# Base_station_Unit_board.net
KiCad netlist of a schematic drawn in Altium Designer
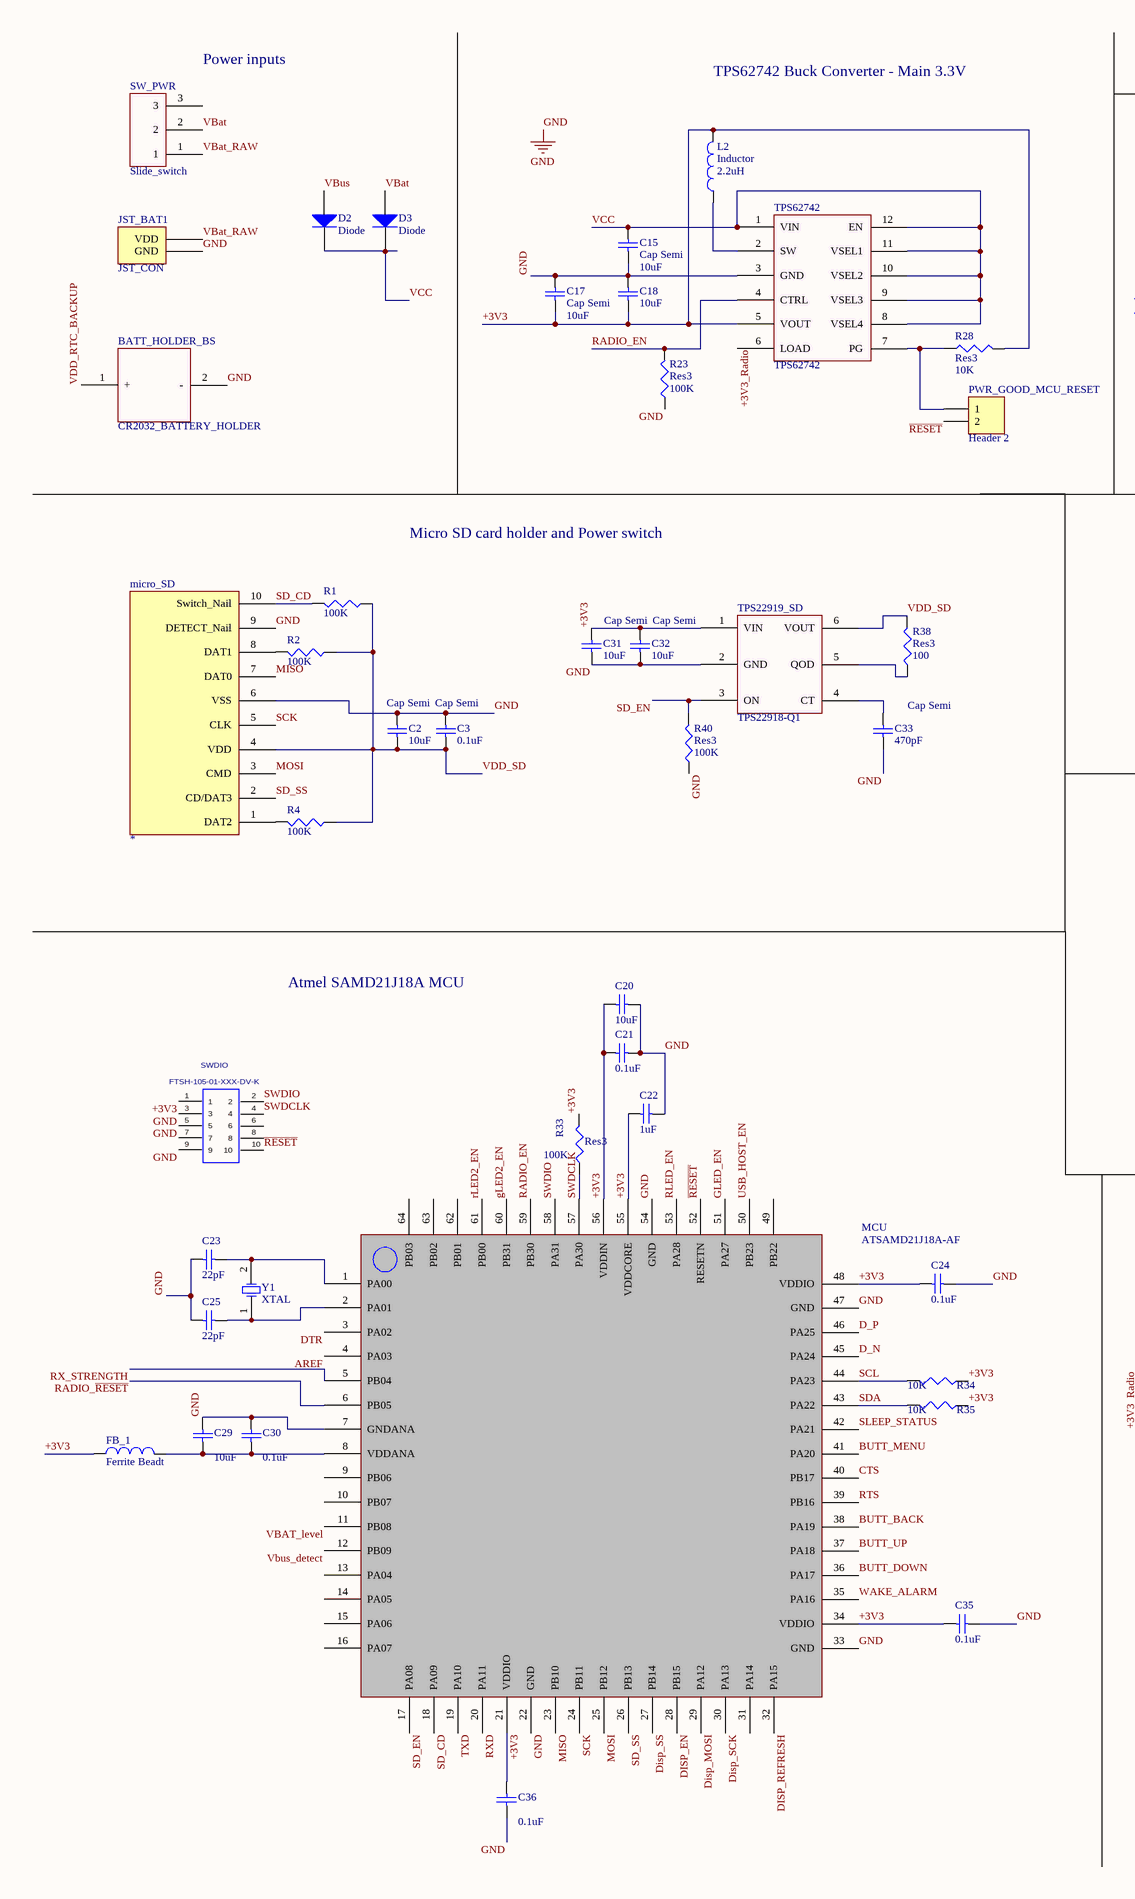
[diagram p0: Base_station_Unit_board.SchDoc, left]
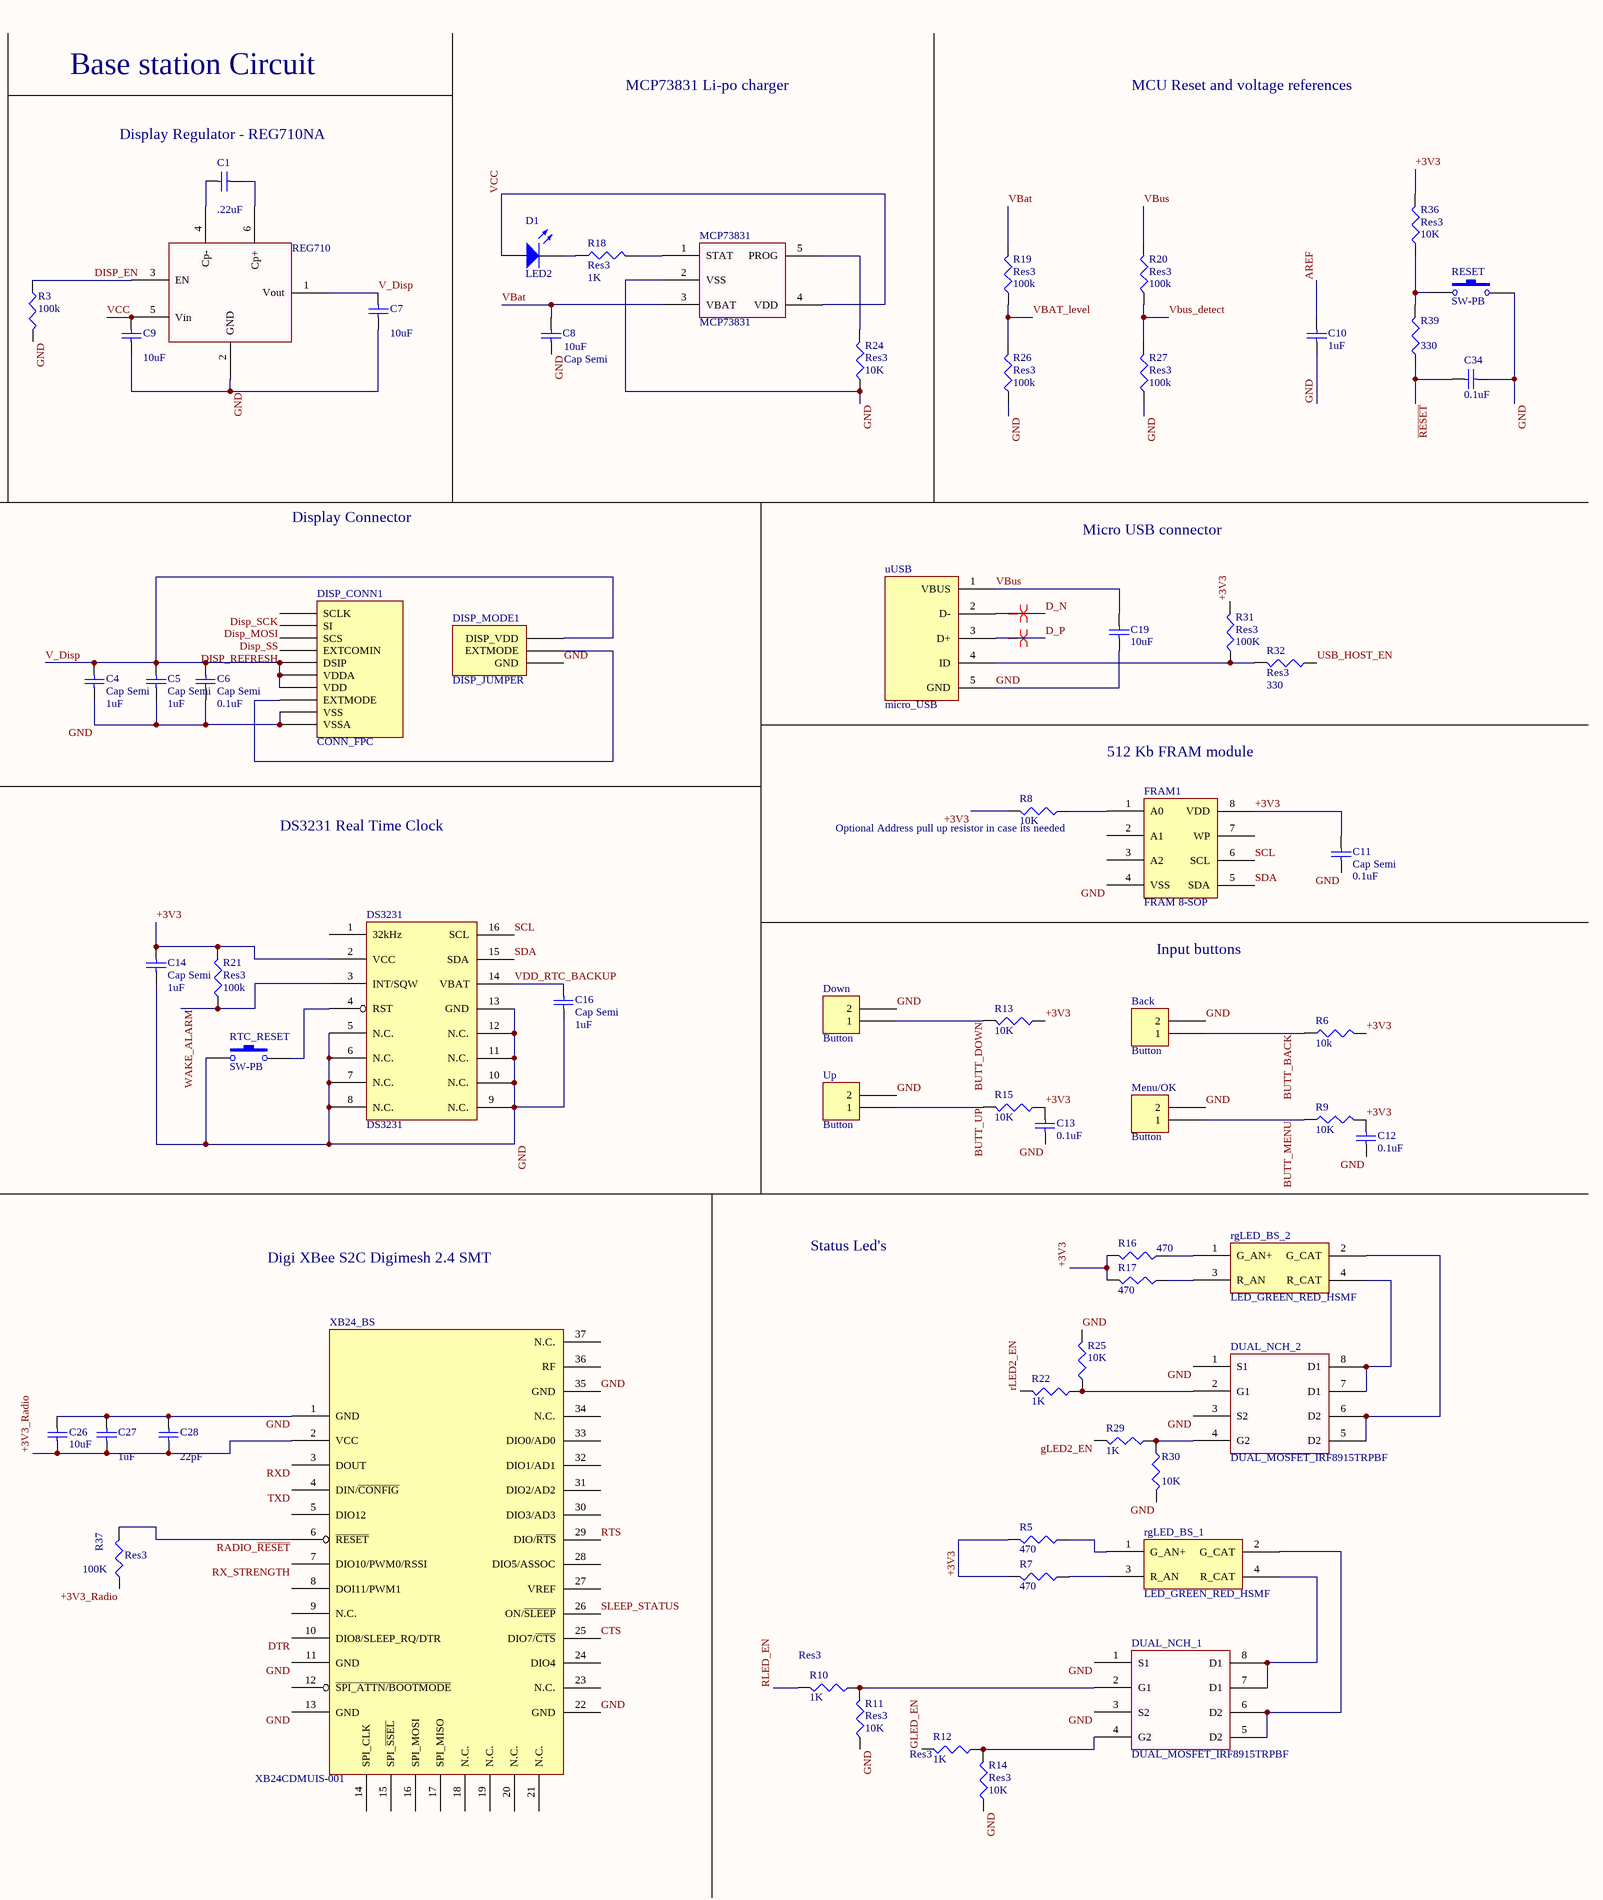
[diagram p1: Base_station_Unit_board.SchDoc, right]

(export (version "E")
  (design (tool "Eeschema 10.0.6"))
  (components
    (comp (ref "Back")
      (value "Button")
      (footprint "EVPASCB1A - Tactile Switch")
      (libsource (lib "Parts_Schematic") (part "Button"))
    )
    (comp (ref "BATT_HOLDER_BS")
      (value "CR2032_BATTERY_HOLDER")
      (footprint "CR1220_clip")
      (libsource (lib "SMD_components") (part "CR2032_BATTERY_HOLDER"))
    )
    (comp (ref "C1")
      (value ".22uF")
      (footprint "C0805")
      (description "Capacitor (Semiconductor SIM Model)")
      (fields (field (name "Comment") "Cap Semi") (field (name "PUBLISHER") "Altium Limited"))
      (libsource (lib "Miscellaneous Devices") (part "Cap Semi"))
    )
    (comp (ref "C2")
      (value "Cap Semi")
      (footprint "1608[0603]")
      (description "Capacitor (Semiconductor SIM Model)")
      (fields (field (name "ALTIUM_VALUE") "10uF") (field (name "PUBLISHER") "Altium Limited"))
      (libsource (lib "Miscellaneous Devices") (part "Cap Semi"))
    )
    (comp (ref "C3")
      (value "Cap Semi")
      (footprint "C0805")
      (description "Capacitor (Semiconductor SIM Model)")
      (fields (field (name "ALTIUM_VALUE") "0.1uF") (field (name "PUBLISHER") "Altium Limited"))
      (libsource (lib "Miscellaneous Devices") (part "Cap Semi"))
    )
    (comp (ref "C4")
      (value "Cap Semi")
      (footprint "C0805")
      (description "Capacitor (Semiconductor SIM Model)")
      (fields (field (name "ALTIUM_VALUE") "1uF") (field (name "PUBLISHER") "Altium Limited"))
      (libsource (lib "Miscellaneous Devices") (part "Cap Semi"))
    )
    (comp (ref "C5")
      (value "Cap Semi")
      (footprint "C0805")
      (description "Capacitor (Semiconductor SIM Model)")
      (fields (field (name "ALTIUM_VALUE") "1uF") (field (name "PUBLISHER") "Altium Limited"))
      (libsource (lib "Miscellaneous Devices") (part "Cap Semi"))
    )
    (comp (ref "C6")
      (value "Cap Semi")
      (footprint "C0805")
      (description "Capacitor (Semiconductor SIM Model)")
      (fields (field (name "ALTIUM_VALUE") "0.1uF") (field (name "PUBLISHER") "Altium Limited"))
      (libsource (lib "Miscellaneous Devices") (part "Cap Semi"))
    )
    (comp (ref "C7")
      (value "10uF")
      (footprint "1608[0603]")
      (description "Capacitor (Semiconductor SIM Model)")
      (fields (field (name "Comment") "Cap Semi") (field (name "PUBLISHER") "Altium Limited"))
      (libsource (lib "Miscellaneous Devices") (part "Cap Semi"))
    )
    (comp (ref "C8")
      (value "Cap Semi")
      (footprint "1608[0603]")
      (description "Capacitor (Semiconductor SIM Model)")
      (fields (field (name "ALTIUM_VALUE") "10uF") (field (name "PUBLISHER") "Altium Limited"))
      (libsource (lib "Miscellaneous Devices") (part "Cap Semi"))
    )
    (comp (ref "C9")
      (value "10uF")
      (footprint "1608[0603]")
      (description "Capacitor (Semiconductor SIM Model)")
      (fields (field (name "Comment") "Cap Semi") (field (name "PUBLISHER") "Altium Limited"))
      (libsource (lib "Miscellaneous Devices") (part "Cap Semi"))
    )
    (comp (ref "C10")
      (value "1uF")
      (footprint "C0805")
      (description "Capacitor (Semiconductor SIM Model)")
      (fields (field (name "Comment") "Cap Semi") (field (name "PUBLISHER") "Altium Limited"))
      (libsource (lib "Miscellaneous Devices") (part "Cap Semi"))
    )
    (comp (ref "C11")
      (value "Cap Semi")
      (footprint "C0805")
      (description "Capacitor (Semiconductor SIM Model)")
      (fields (field (name "ALTIUM_VALUE") "0.1uF") (field (name "PUBLISHER") "Altium Limited"))
      (libsource (lib "Miscellaneous Devices") (part "Cap Semi"))
    )
    (comp (ref "C12")
      (value "0.1uF")
      (footprint "C0805")
      (description "Capacitor (Semiconductor SIM Model)")
      (fields (field (name "Comment") "Cap Semi") (field (name "PUBLISHER") "Altium Limited"))
      (libsource (lib "Miscellaneous Devices") (part "Cap Semi"))
    )
    (comp (ref "C13")
      (value "0.1uF")
      (footprint "C0805")
      (description "Capacitor (Semiconductor SIM Model)")
      (fields (field (name "Comment") "Cap Semi") (field (name "PUBLISHER") "Altium Limited"))
      (libsource (lib "Miscellaneous Devices") (part "Cap Semi"))
    )
    (comp (ref "C14")
      (value "Cap Semi")
      (footprint "C0805")
      (description "Capacitor (Semiconductor SIM Model)")
      (fields (field (name "ALTIUM_VALUE") "1uF") (field (name "PUBLISHER") "Altium Limited"))
      (libsource (lib "Miscellaneous Devices") (part "Cap Semi"))
    )
    (comp (ref "C15")
      (value "Cap Semi")
      (footprint "1608[0603]")
      (description "Capacitor (Semiconductor SIM Model)")
      (fields (field (name "ALTIUM_VALUE") "10uF") (field (name "PUBLISHER") "Altium Limited"))
      (libsource (lib "Miscellaneous Devices") (part "Cap Semi"))
    )
    (comp (ref "C16")
      (value "Cap Semi")
      (footprint "C0805")
      (description "Capacitor (Semiconductor SIM Model)")
      (fields (field (name "ALTIUM_VALUE") "1uF") (field (name "PUBLISHER") "Altium Limited"))
      (libsource (lib "Miscellaneous Devices") (part "Cap Semi"))
    )
    (comp (ref "C17")
      (value "Cap Semi")
      (footprint "1608[0603]")
      (description "Capacitor (Semiconductor SIM Model)")
      (fields (field (name "ALTIUM_VALUE") "10uF") (field (name "PUBLISHER") "Altium Limited"))
      (libsource (lib "Miscellaneous Devices") (part "Cap Semi"))
    )
    (comp (ref "C18")
      (value "10uF")
      (footprint "1608[0603]")
      (description "Capacitor (Semiconductor SIM Model)")
      (fields (field (name "Comment") "Cap Semi") (field (name "PUBLISHER") "Altium Limited"))
      (libsource (lib "Miscellaneous Devices") (part "Cap Semi"))
    )
    (comp (ref "C19")
      (value "10uF")
      (footprint "1608[0603]")
      (description "Capacitor (Semiconductor SIM Model)")
      (fields (field (name "Comment") "Cap Semi") (field (name "PUBLISHER") "Altium Limited"))
      (libsource (lib "Miscellaneous Devices") (part "Cap Semi"))
    )
    (comp (ref "C20")
      (value "10uF")
      (footprint "1608[0603]")
      (description "Capacitor (Semiconductor SIM Model)")
      (fields (field (name "Comment") "Cap Semi") (field (name "PUBLISHER") "Altium Limited"))
      (libsource (lib "Miscellaneous Devices") (part "Cap Semi"))
    )
    (comp (ref "C21")
      (value "0.1uF")
      (footprint "C0805")
      (description "Capacitor (Semiconductor SIM Model)")
      (fields (field (name "Comment") "Cap Semi") (field (name "PUBLISHER") "Altium Limited"))
      (libsource (lib "Miscellaneous Devices") (part "Cap Semi"))
    )
    (comp (ref "C22")
      (value "1uF")
      (footprint "C0805")
      (description "Capacitor (Semiconductor SIM Model)")
      (fields (field (name "Comment") "Cap Semi") (field (name "PUBLISHER") "Altium Limited"))
      (libsource (lib "Miscellaneous Devices") (part "Cap Semi"))
    )
    (comp (ref "C23")
      (value "22pF")
      (footprint "1608[0603]")
      (description "Capacitor (Semiconductor SIM Model)")
      (fields (field (name "Comment") "Cap Semi") (field (name "PUBLISHER") "Altium Limited"))
      (libsource (lib "Miscellaneous Devices") (part "Cap Semi"))
    )
    (comp (ref "C24")
      (value "0.1uF")
      (footprint "C0805")
      (description "Capacitor (Semiconductor SIM Model)")
      (fields (field (name "Comment") "Cap Semi") (field (name "PUBLISHER") "Altium Limited"))
      (libsource (lib "Miscellaneous Devices") (part "Cap Semi"))
    )
    (comp (ref "C25")
      (value "22pF")
      (footprint "1608[0603]")
      (description "Capacitor (Semiconductor SIM Model)")
      (fields (field (name "Comment") "Cap Semi") (field (name "PUBLISHER") "Altium Limited"))
      (libsource (lib "Miscellaneous Devices") (part "Cap Semi"))
    )
    (comp (ref "C26")
      (value "10uF")
      (footprint "1608[0603]")
      (description "Capacitor (Semiconductor SIM Model)")
      (fields (field (name "Comment") "Cap Semi") (field (name "PUBLISHER") "Altium Limited"))
      (libsource (lib "Miscellaneous Devices") (part "Cap Semi"))
    )
    (comp (ref "C27")
      (value "1uF")
      (footprint "C0805")
      (description "Capacitor (Semiconductor SIM Model)")
      (fields (field (name "Comment") "Cap Semi") (field (name "PUBLISHER") "Altium Limited"))
      (libsource (lib "Miscellaneous Devices") (part "Cap Semi"))
    )
    (comp (ref "C28")
      (value "22pF")
      (footprint "1608[0603]")
      (description "Capacitor (Semiconductor SIM Model)")
      (fields (field (name "Comment") "Cap Semi") (field (name "PUBLISHER") "Altium Limited"))
      (libsource (lib "Miscellaneous Devices") (part "Cap Semi"))
    )
    (comp (ref "C29")
      (value "10uF")
      (footprint "1608[0603]")
      (description "Capacitor (Semiconductor SIM Model)")
      (fields (field (name "Comment") "Cap Semi") (field (name "PUBLISHER") "Altium Limited"))
      (libsource (lib "Miscellaneous Devices") (part "Cap Semi"))
    )
    (comp (ref "C30")
      (value "0.1uF")
      (footprint "C0805")
      (description "Capacitor (Semiconductor SIM Model)")
      (fields (field (name "Comment") "Cap Semi") (field (name "PUBLISHER") "Altium Limited"))
      (libsource (lib "Miscellaneous Devices") (part "Cap Semi"))
    )
    (comp (ref "C31")
      (value "Cap Semi")
      (footprint "C0805")
      (description "Capacitor (Semiconductor SIM Model)")
      (fields (field (name "ALTIUM_VALUE") "10uF") (field (name "PUBLISHER") "Altium Limited"))
      (libsource (lib "Miscellaneous Devices") (part "Cap Semi"))
    )
    (comp (ref "C32")
      (value "Cap Semi")
      (footprint "C0805")
      (description "Capacitor (Semiconductor SIM Model)")
      (fields (field (name "ALTIUM_VALUE") "10uF") (field (name "PUBLISHER") "Altium Limited"))
      (libsource (lib "Miscellaneous Devices") (part "Cap Semi"))
    )
    (comp (ref "C33")
      (value "Cap Semi")
      (footprint "C0805")
      (description "Capacitor (Semiconductor SIM Model)")
      (fields (field (name "ALTIUM_VALUE") "470pF") (field (name "PUBLISHER") "Altium Limited"))
      (libsource (lib "Miscellaneous Devices") (part "Cap Semi"))
    )
    (comp (ref "C34")
      (value "0.1uF")
      (footprint "C0805")
      (description "Capacitor (Semiconductor SIM Model)")
      (fields (field (name "Comment") "Cap Semi") (field (name "PUBLISHER") "Altium Limited"))
      (libsource (lib "Miscellaneous Devices") (part "Cap Semi"))
    )
    (comp (ref "C35")
      (value "0.1uF")
      (footprint "C0805")
      (description "Capacitor (Semiconductor SIM Model)")
      (fields (field (name "Comment") "Cap Semi") (field (name "PUBLISHER") "Altium Limited"))
      (libsource (lib "Miscellaneous Devices") (part "Cap Semi"))
    )
    (comp (ref "C36")
      (value "0.1uF")
      (footprint "C0805")
      (description "Capacitor (Semiconductor SIM Model)")
      (fields (field (name "Comment") "Cap Semi") (field (name "PUBLISHER") "Altium Limited"))
      (libsource (lib "Miscellaneous Devices") (part "Cap Semi"))
    )
    (comp (ref "D1")
      (value "LED2")
      (footprint "LED_Single_Orange")
      (description "Typical RED, GREEN, YELLOW, AMBER GaAs LED")
      (fields (field (name "PUBLISHER") "Altium Limited"))
      (libsource (lib "Miscellaneous Devices") (part "LED2"))
    )
    (comp (ref "D2")
      (value "Diode")
      (footprint "DO-214AC")
      (description "Default Diode")
      (fields (field (name "PUBLISHER") "Altium Limited"))
      (libsource (lib "Miscellaneous Devices") (part "Diode"))
    )
    (comp (ref "D3")
      (value "Diode")
      (footprint "DO-214AC")
      (description "Default Diode")
      (fields (field (name "PUBLISHER") "Altium Limited"))
      (libsource (lib "Miscellaneous Devices") (part "Diode"))
    )
    (comp (ref "DISP_CONN1")
      (value "CONN_FPC")
      (footprint "CONN_FPC")
      (libsource (lib "Parts_Schematic") (part "CONN_FPC"))
    )
    (comp (ref "DISP_MODE1")
      (value "DISP_JUMPER")
      (footprint "DISP_Jumper")
      (libsource (lib "Parts_Schematic") (part "DISP_JUMPER"))
    )
    (comp (ref "Down")
      (value "Button")
      (footprint "EVPASCB1A - Tactile Switch")
      (libsource (lib "Parts_Schematic") (part "Button"))
    )
    (comp (ref "DS3231")
      (value "DS3231")
      (footprint "16 SO")
      (libsource (lib "SMD_components") (part "DS3231"))
    )
    (comp (ref "DUAL_NCH_1")
      (value "DUAL_MOSFET_IRF8915TRPBF")
      (footprint "SOP-8")
      (libsource (lib "SMD_components") (part "DUAL_MOSFET_IRF8915TRPBF"))
    )
    (comp (ref "DUAL_NCH_2")
      (value "DUAL_MOSFET_IRF8915TRPBF")
      (footprint "SOP-8")
      (libsource (lib "SMD_components") (part "DUAL_MOSFET_IRF8915TRPBF"))
    )
    (comp (ref "FB_1")
      (value "Ferrite Beadt")
      (footprint "FERRITE_BEAD")
      (description "Inductor")
      (fields (field (name "PUBLISHER") "Altium Limited"))
      (libsource (lib "Miscellaneous Devices") (part "Inductor"))
    )
    (comp (ref "FRAM1")
      (value "FRAM 8-SOP")
      (footprint "SOP-8")
      (libsource (lib "SMD_components") (part "FRAM 8-SOP"))
    )
    (comp (ref "JST_BAT1")
      (value "JST_CON")
      (footprint "JST_CONN_SMT_Vertical")
      (libsource (lib "Parts_Schematic") (part "JST_CON"))
    )
    (comp (ref "L2")
      (value "Inductor")
      (footprint "2.2uH_Inductor")
      (fields (field (name "ALTIUM_VALUE") "2.2uH") (field (name "PUBLISHER") "Altium Limited"))
      (libsource (lib "Miscellaneous Devices") (part "Inductor"))
    )
    (comp (ref "MCP73831")
      (value "MCP73831")
      (footprint "SOT-23")
      (libsource (lib "SMD_components") (part "MCP73831"))
    )
    (comp (ref "MCU")
      (value "ATSAMD21J18A-AF")
      (footprint "QFN64_rect_medPin")
      (libsource (lib "SMD_components") (part "ATSAMD21J18A-AF"))
    )
    (comp (ref "Menu/OK")
      (value "Button")
      (footprint "EVPASCB1A - Tactile Switch")
      (libsource (lib "Parts_Schematic") (part "Button"))
    )
    (comp (ref "micro_SD")
      (value "*")
      (footprint "MicroSD_Connector")
      (libsource (lib "SMD_components") (part "micro_SD"))
    )
    (comp (ref "PWR_GOOD_MCU_RESET")
      (value "Header 2")
      (footprint "SMD_Jumper")
      (description "Header, 2-Pin")
      (fields (field (name "PUBLISHER") "Altium Limited"))
      (libsource (lib "Miscellaneous Connectors") (part "Header 2"))
    )
    (comp (ref "R1")
      (value "100K")
      (footprint "6-0805_N")
      (description "Resistor")
      (fields (field (name "Comment") "Res3") (field (name "PUBLISHER") "Altium Limited"))
      (libsource (lib "Miscellaneous Devices") (part "Res3"))
    )
    (comp (ref "R2")
      (value "100K")
      (footprint "6-0805_N")
      (description "Resistor")
      (fields (field (name "Comment") "Res3") (field (name "PUBLISHER") "Altium Limited"))
      (libsource (lib "Miscellaneous Devices") (part "Res3"))
    )
    (comp (ref "R3")
      (value "100k")
      (footprint "6-0805_N")
      (description "Resistor")
      (fields (field (name "Comment") "Res3") (field (name "PUBLISHER") "Altium Limited"))
      (libsource (lib "Miscellaneous Devices") (part "Res3"))
    )
    (comp (ref "R4")
      (value "100K")
      (footprint "6-0805_N")
      (description "Resistor")
      (fields (field (name "Comment") "Res3") (field (name "PUBLISHER") "Altium Limited"))
      (libsource (lib "Miscellaneous Devices") (part "Res3"))
    )
    (comp (ref "R5")
      (value "470")
      (footprint "6-0805_N")
      (description "Resistor")
      (fields (field (name "Comment") "Res3") (field (name "PUBLISHER") "Altium Limited"))
      (libsource (lib "Miscellaneous Devices") (part "Res3"))
    )
    (comp (ref "R6")
      (value "10k")
      (footprint "6-0805_N")
      (description "Resistor")
      (fields (field (name "Comment") "Res3") (field (name "PUBLISHER") "Altium Limited"))
      (libsource (lib "Miscellaneous Devices") (part "Res3"))
    )
    (comp (ref "R7")
      (value "470")
      (footprint "6-0805_N")
      (description "Resistor")
      (fields (field (name "Comment") "Res3") (field (name "PUBLISHER") "Altium Limited"))
      (libsource (lib "Miscellaneous Devices") (part "Res3"))
    )
    (comp (ref "R8")
      (value "10K")
      (footprint "6-0805_N")
      (description "Resistor")
      (fields (field (name "Comment") "Res3") (field (name "PUBLISHER") "Altium Limited"))
      (libsource (lib "Miscellaneous Devices") (part "Res3"))
    )
    (comp (ref "R9")
      (value "10K")
      (footprint "6-0805_N")
      (description "Resistor")
      (fields (field (name "Comment") "Res3") (field (name "PUBLISHER") "Altium Limited"))
      (libsource (lib "Miscellaneous Devices") (part "Res3"))
    )
    (comp (ref "R10")
      (value "Res3")
      (footprint "6-0805_N")
      (description "Resistor")
      (fields (field (name "ALTIUM_VALUE") "1K") (field (name "PUBLISHER") "Altium Limited"))
      (libsource (lib "Miscellaneous Devices") (part "Res3"))
    )
    (comp (ref "R11")
      (value "Res3")
      (footprint "6-0805_N")
      (description "Resistor")
      (fields (field (name "ALTIUM_VALUE") "10K") (field (name "PUBLISHER") "Altium Limited"))
      (libsource (lib "Miscellaneous Devices") (part "Res3"))
    )
    (comp (ref "R12")
      (value "Res3")
      (footprint "6-0805_N")
      (description "Resistor")
      (fields (field (name "ALTIUM_VALUE") "1K") (field (name "PUBLISHER") "Altium Limited"))
      (libsource (lib "Miscellaneous Devices") (part "Res3"))
    )
    (comp (ref "R13")
      (value "10K")
      (footprint "6-0805_N")
      (description "Resistor")
      (fields (field (name "Comment") "Res3") (field (name "PUBLISHER") "Altium Limited"))
      (libsource (lib "Miscellaneous Devices") (part "Res3"))
    )
    (comp (ref "R14")
      (value "Res3")
      (footprint "6-0805_N")
      (description "Resistor")
      (fields (field (name "ALTIUM_VALUE") "10K") (field (name "PUBLISHER") "Altium Limited"))
      (libsource (lib "Miscellaneous Devices") (part "Res3"))
    )
    (comp (ref "R15")
      (value "10K")
      (footprint "6-0805_N")
      (description "Resistor")
      (fields (field (name "Comment") "Res3") (field (name "PUBLISHER") "Altium Limited"))
      (libsource (lib "Miscellaneous Devices") (part "Res3"))
    )
    (comp (ref "R16")
      (value "470")
      (footprint "6-0805_N")
      (description "Resistor")
      (fields (field (name "Comment") "Res3") (field (name "PUBLISHER") "Altium Limited"))
      (libsource (lib "Miscellaneous Devices") (part "Res3"))
    )
    (comp (ref "R17")
      (value "470")
      (footprint "6-0805_N")
      (description "Resistor")
      (fields (field (name "Comment") "Res3") (field (name "PUBLISHER") "Altium Limited"))
      (libsource (lib "Miscellaneous Devices") (part "Res3"))
    )
    (comp (ref "R18")
      (value "Res3")
      (footprint "6-0805_N")
      (description "Resistor")
      (fields (field (name "ALTIUM_VALUE") "1K") (field (name "PUBLISHER") "Altium Limited"))
      (libsource (lib "Miscellaneous Devices") (part "Res3"))
    )
    (comp (ref "R19")
      (value "Res3")
      (footprint "6-0805_N")
      (description "Resistor")
      (fields (field (name "ALTIUM_VALUE") "100k") (field (name "PUBLISHER") "Altium Limited"))
      (libsource (lib "Miscellaneous Devices") (part "Res3"))
    )
    (comp (ref "R20")
      (value "Res3")
      (footprint "6-0805_N")
      (description "Resistor")
      (fields (field (name "ALTIUM_VALUE") "100k") (field (name "PUBLISHER") "Altium Limited"))
      (libsource (lib "Miscellaneous Devices") (part "Res3"))
    )
    (comp (ref "R21")
      (value "Res3")
      (footprint "6-0805_N")
      (description "Resistor")
      (fields (field (name "ALTIUM_VALUE") "100k") (field (name "PUBLISHER") "Altium Limited"))
      (libsource (lib "Miscellaneous Devices") (part "Res3"))
    )
    (comp (ref "R22")
      (value "1K")
      (footprint "6-0805_N")
      (description "Resistor")
      (fields (field (name "Comment") "Res3") (field (name "PUBLISHER") "Altium Limited"))
      (libsource (lib "Miscellaneous Devices") (part "Res3"))
    )
    (comp (ref "R23")
      (value "Res3")
      (footprint "6-0805_N")
      (description "Resistor")
      (fields (field (name "ALTIUM_VALUE") "100K") (field (name "PUBLISHER") "Altium Limited"))
      (libsource (lib "Miscellaneous Devices") (part "Res3"))
    )
    (comp (ref "R24")
      (value "Res3")
      (footprint "6-0805_N")
      (description "Resistor")
      (fields (field (name "ALTIUM_VALUE") "10K") (field (name "PUBLISHER") "Altium Limited"))
      (libsource (lib "Miscellaneous Devices") (part "Res3"))
    )
    (comp (ref "R25")
      (value "10K")
      (footprint "6-0805_N")
      (description "Resistor")
      (fields (field (name "Comment") "Res3") (field (name "PUBLISHER") "Altium Limited"))
      (libsource (lib "Miscellaneous Devices") (part "Res3"))
    )
    (comp (ref "R26")
      (value "Res3")
      (footprint "6-0805_N")
      (description "Resistor")
      (fields (field (name "ALTIUM_VALUE") "100k") (field (name "PUBLISHER") "Altium Limited"))
      (libsource (lib "Miscellaneous Devices") (part "Res3"))
    )
    (comp (ref "R27")
      (value "Res3")
      (footprint "6-0805_N")
      (description "Resistor")
      (fields (field (name "ALTIUM_VALUE") "100k") (field (name "PUBLISHER") "Altium Limited"))
      (libsource (lib "Miscellaneous Devices") (part "Res3"))
    )
    (comp (ref "R28")
      (value "Res3")
      (footprint "6-0805_N")
      (description "Resistor")
      (fields (field (name "ALTIUM_VALUE") "10K") (field (name "PUBLISHER") "Altium Limited"))
      (libsource (lib "Miscellaneous Devices") (part "Res3"))
    )
    (comp (ref "R29")
      (value "1K")
      (footprint "6-0805_N")
      (description "Resistor")
      (fields (field (name "Comment") "Res3") (field (name "PUBLISHER") "Altium Limited"))
      (libsource (lib "Miscellaneous Devices") (part "Res3"))
    )
    (comp (ref "R30")
      (value "10K")
      (footprint "6-0805_N")
      (description "Resistor")
      (fields (field (name "Comment") "Res3") (field (name "PUBLISHER") "Altium Limited"))
      (libsource (lib "Miscellaneous Devices") (part "Res3"))
    )
    (comp (ref "R31")
      (value "Res3")
      (footprint "6-0805_N")
      (description "Resistor")
      (fields (field (name "ALTIUM_VALUE") "100K") (field (name "PUBLISHER") "Altium Limited"))
      (libsource (lib "Miscellaneous Devices") (part "Res3"))
    )
    (comp (ref "R32")
      (value "Res3")
      (footprint "6-0805_N")
      (description "Resistor")
      (fields (field (name "ALTIUM_VALUE") "330") (field (name "PUBLISHER") "Altium Limited"))
      (libsource (lib "Miscellaneous Devices") (part "Res3"))
    )
    (comp (ref "R33")
      (value "Res3")
      (footprint "6-0805_N")
      (description "Resistor")
      (fields (field (name "ALTIUM_VALUE") "100K") (field (name "PUBLISHER") "Altium Limited"))
      (libsource (lib "Miscellaneous Devices") (part "Res3"))
    )
    (comp (ref "R34")
      (value "10K")
      (footprint "6-0805_N")
      (description "Resistor")
      (fields (field (name "Comment") "Res3") (field (name "PUBLISHER") "Altium Limited"))
      (libsource (lib "Miscellaneous Devices") (part "Res3"))
    )
    (comp (ref "R35")
      (value "10K")
      (footprint "6-0805_N")
      (description "Resistor")
      (fields (field (name "Comment") "Res3") (field (name "PUBLISHER") "Altium Limited"))
      (libsource (lib "Miscellaneous Devices") (part "Res3"))
    )
    (comp (ref "R36")
      (value "Res3")
      (footprint "6-0805_N")
      (description "Resistor")
      (fields (field (name "ALTIUM_VALUE") "10K") (field (name "PUBLISHER") "Altium Limited"))
      (libsource (lib "Miscellaneous Devices") (part "Res3"))
    )
    (comp (ref "R37")
      (value "Res3")
      (footprint "6-0805_N")
      (description "Resistor")
      (fields (field (name "ALTIUM_VALUE") "100K") (field (name "PUBLISHER") "Altium Limited"))
      (libsource (lib "Miscellaneous Devices") (part "Res3"))
    )
    (comp (ref "R38")
      (value "Res3")
      (footprint "6-0805_N")
      (description "Resistor")
      (fields (field (name "ALTIUM_VALUE") "100") (field (name "PUBLISHER") "Altium Limited"))
      (libsource (lib "Miscellaneous Devices") (part "Res3"))
    )
    (comp (ref "R39")
      (value "330")
      (footprint "6-0805_N")
      (description "Resistor")
      (fields (field (name "Comment") "Res3") (field (name "PUBLISHER") "Altium Limited"))
      (libsource (lib "Miscellaneous Devices") (part "Res3"))
    )
    (comp (ref "R40")
      (value "Res3")
      (footprint "6-0805_N")
      (description "Resistor")
      (fields (field (name "ALTIUM_VALUE") "100K") (field (name "PUBLISHER") "Altium Limited"))
      (libsource (lib "Miscellaneous Devices") (part "Res3"))
    )
    (comp (ref "REG710")
      (value "REG710NA-5/3K")
      (footprint "SOT-23-6")
      (libsource (lib "SMD_components") (part "REG710NA-5/3K"))
    )
    (comp (ref "RESET")
      (value "SW-PB")
      (footprint "SW_TACTILE")
      (description "Switch")
      (fields (field (name "PUBLISHER") "Altium Limited"))
      (libsource (lib "Miscellaneous Devices") (part "SW-PB"))
    )
    (comp (ref "rgLED_BS_1")
      (value "LED_GREEN_RED_HSMF")
      (footprint "LED4")
      (libsource (lib "SMD_components") (part "LED_GREEN_RED_HSMF"))
    )
    (comp (ref "rgLED_BS_2")
      (value "LED_GREEN_RED_HSMF")
      (footprint "LED4")
      (libsource (lib "SMD_components") (part "LED_GREEN_RED_HSMF"))
    )
    (comp (ref "RTC_RESET")
      (value "SW-PB")
      (footprint "SW_TACTILE")
      (description "Switch")
      (fields (field (name "PUBLISHER") "Altium Limited"))
      (libsource (lib "Miscellaneous Devices") (part "SW-PB"))
    )
    (comp (ref "SWDIO")
      (value "FTSH-105-01-XXX-DV-K")
      (footprint "FTSH-105-01-XXX-DV-K")
      (description "TERMINAL STRIP, .050\"(1.27mm) PITCH, 10 PINS, KEYED")
      (fields (field (name "MANUFACTURER") "SAMTEC") (field (name "CREATED") "November 30, 2016 - Wendy Xin"))
      (libsource (lib "FTSH-105-01-XXX-DV-K") (part "FTSH-105-01-XXX-DV-K"))
    )
    (comp (ref "SW_PWR")
      (value "Slide_switch")
      (footprint "Slide_SW")
      (libsource (lib "SMD_components") (part "Slide_switch"))
    )
    (comp (ref "TPS22919_SD")
      (value "TPS22918-Q1")
      (footprint "SOT-23-6")
      (libsource (lib "SMD_components") (part "TPS22918-Q1"))
    )
    (comp (ref "TPS62742")
      (value "TPS62742")
      (footprint "WSON12 - small")
      (libsource (lib "SMD_components") (part "TPS62742"))
    )
    (comp (ref "Up")
      (value "Button")
      (footprint "EVPASCB1A - Tactile Switch")
      (libsource (lib "Parts_Schematic") (part "Button"))
    )
    (comp (ref "uUSB")
      (value "micro_USB")
      (footprint "MicroUSB_CONN")
      (libsource (lib "SMD_components") (part "micro_USB"))
    )
    (comp (ref "XB24_BS")
      (value "XB24CDMUIS-001")
      (footprint "XB24_RADIO")
      (libsource (lib "SMD_components") (part "XB24CDMUIS-001"))
    )
    (comp (ref "Y1")
      (value "XTAL")
      (footprint "ABS07_Crystal")
      (description "Crystal Oscillator")
      (fields (field (name "PUBLISHER") "Altium Limited"))
      (libsource (lib "Miscellaneous Devices") (part "XTAL"))
    )
  )
  (nets
    (net (code "1") (name "/+3V3") (class "Default")
      (node (ref "C11") (pin "2") (pinfunction "2_2") (pintype "passive"))
      (node (ref "C12") (pin "2") (pinfunction "2_2") (pintype "passive"))
      (node (ref "C13") (pin "2") (pinfunction "2_2") (pintype "passive"))
      (node (ref "C14") (pin "2") (pinfunction "2_2") (pintype "passive"))
      (node (ref "C17") (pin "2") (pinfunction "2_2") (pintype "passive"))
      (node (ref "C18") (pin "1") (pinfunction "1_1") (pintype "passive"))
      (node (ref "C20") (pin "2") (pinfunction "2_2") (pintype "passive"))
      (node (ref "C21") (pin "2") (pinfunction "2_2") (pintype "passive"))
      (node (ref "C22") (pin "2") (pinfunction "2_2") (pintype "passive"))
      (node (ref "C24") (pin "2") (pinfunction "2_2") (pintype "passive"))
      (node (ref "C31") (pin "1") (pinfunction "1_1") (pintype "passive"))
      (node (ref "C32") (pin "1") (pinfunction "1_1") (pintype "passive"))
      (node (ref "C35") (pin "2") (pinfunction "2_2") (pintype "passive"))
      (node (ref "C36") (pin "2") (pinfunction "2_2") (pintype "passive"))
      (node (ref "DS3231") (pin "2") (pinfunction "VCC_2") (pintype "passive"))
      (node (ref "FB_1") (pin "1") (pinfunction "1_1") (pintype "passive"))
      (node (ref "FRAM1") (pin "8") (pinfunction "VDD_8") (pintype "passive"))
      (node (ref "L2") (pin "2") (pinfunction "2_2") (pintype "passive"))
      (node (ref "MCU") (pin "21") (pinfunction "VDDIO_21") (pintype "passive"))
      (node (ref "MCU") (pin "34") (pinfunction "VDDIO_34") (pintype "passive"))
      (node (ref "MCU") (pin "48") (pinfunction "VDDIO_48") (pintype "passive"))
      (node (ref "MCU") (pin "55") (pinfunction "VDDCORE_55") (pintype "passive"))
      (node (ref "MCU") (pin "56") (pinfunction "VDDIN_56") (pintype "passive"))
      (node (ref "R13") (pin "1") (pinfunction "1_1") (pintype "passive"))
      (node (ref "R15") (pin "1") (pinfunction "1_1") (pintype "passive"))
      (node (ref "R16") (pin "2") (pinfunction "2_2") (pintype "passive"))
      (node (ref "R17") (pin "2") (pinfunction "2_2") (pintype "passive"))
      (node (ref "R21") (pin "2") (pinfunction "2_2") (pintype "passive"))
      (node (ref "R28") (pin "2") (pinfunction "2_2") (pintype "passive"))
      (node (ref "R31") (pin "2") (pinfunction "2_2") (pintype "passive"))
      (node (ref "R33") (pin "2") (pinfunction "2_2") (pintype "passive"))
      (node (ref "R34") (pin "1") (pinfunction "1_1") (pintype "passive"))
      (node (ref "R35") (pin "1") (pinfunction "1_1") (pintype "passive"))
      (node (ref "R36") (pin "2") (pinfunction "2_2") (pintype "passive"))
      (node (ref "R5") (pin "2") (pinfunction "2_2") (pintype "passive"))
      (node (ref "R6") (pin "2") (pinfunction "2_2") (pintype "passive"))
      (node (ref "R7") (pin "2") (pinfunction "2_2") (pintype "passive"))
      (node (ref "R8") (pin "2") (pinfunction "2_2") (pintype "passive"))
      (node (ref "R9") (pin "2") (pinfunction "2_2") (pintype "passive"))
      (node (ref "SWDIO") (pin "1") (pinfunction "1_1") (pintype "passive"))
      (node (ref "TPS22919_SD") (pin "1") (pinfunction "VIN_1") (pintype "passive"))
      (node (ref "TPS62742") (pin "5") (pinfunction "VOUT_5") (pintype "passive"))
    )
    (net (code "2") (name "/+3V3_Radio") (class "Default")
      (node (ref "C26") (pin "2") (pinfunction "2_2") (pintype "passive"))
      (node (ref "C27") (pin "1") (pinfunction "1_1") (pintype "passive"))
      (node (ref "C28") (pin "1") (pinfunction "1_1") (pintype "passive"))
      (node (ref "R37") (pin "1") (pinfunction "1_1") (pintype "passive"))
      (node (ref "TPS62742") (pin "6") (pinfunction "LOAD_6") (pintype "passive"))
      (node (ref "XB24_BS") (pin "2") (pinfunction "VCC_2") (pintype "passive"))
    )
    (net (code "3") (name "/AREF") (class "Default")
      (node (ref "C10") (pin "1") (pinfunction "1_1") (pintype "passive"))
      (node (ref "MCU") (pin "4") (pinfunction "PA03_4") (pintype "passive"))
    )
    (net (code "4") (name "/BUTT_BACK") (class "Default")
      (node (ref "Back") (pin "1") (pinfunction "1_1") (pintype "passive"))
      (node (ref "MCU") (pin "38") (pinfunction "PA19_38") (pintype "passive"))
      (node (ref "R6") (pin "1") (pinfunction "1_1") (pintype "passive"))
    )
    (net (code "5") (name "/BUTT_DOWN") (class "Default")
      (node (ref "Down") (pin "1") (pinfunction "1_1") (pintype "passive"))
      (node (ref "MCU") (pin "36") (pinfunction "PA17_36") (pintype "passive"))
      (node (ref "R13") (pin "2") (pinfunction "2_2") (pintype "passive"))
    )
    (net (code "6") (name "/BUTT_MENU") (class "Default")
      (node (ref "MCU") (pin "41") (pinfunction "PA20_41") (pintype "passive"))
      (node (ref "Menu/OK") (pin "1") (pinfunction "1_1") (pintype "passive"))
      (node (ref "R9") (pin "1") (pinfunction "1_1") (pintype "passive"))
    )
    (net (code "7") (name "/BUTT_UP") (class "Default")
      (node (ref "MCU") (pin "37") (pinfunction "PA18_37") (pintype "passive"))
      (node (ref "R15") (pin "2") (pinfunction "2_2") (pintype "passive"))
      (node (ref "Up") (pin "1") (pinfunction "1_1") (pintype "passive"))
    )
    (net (code "8") (name "/CTS") (class "Default")
      (node (ref "MCU") (pin "40") (pinfunction "PB17_40") (pintype "passive"))
      (node (ref "XB24_BS") (pin "25") (pinfunction "DIO7/~{CTS}_25") (pintype "passive"))
    )
    (net (code "9") (name "/DISP_EN") (class "Default")
      (node (ref "MCU") (pin "28") (pinfunction "PB15_28") (pintype "passive"))
      (node (ref "R3") (pin "1") (pinfunction "1_1") (pintype "passive"))
      (node (ref "REG710") (pin "3") (pinfunction "EN_3") (pintype "passive"))
    )
    (net (code "10") (name "/DISP_REFRESH") (class "Default")
      (node (ref "DISP_CONN1") (pin "4") (pinfunction "EXTCOMIN_4") (pintype "passive"))
      (node (ref "MCU") (pin "32") (pinfunction "PA15_32") (pintype "passive"))
    )
    (net (code "11") (name "/DTR") (class "Default")
      (node (ref "MCU") (pin "3") (pinfunction "PA02_3") (pintype "passive"))
      (node (ref "XB24_BS") (pin "10") (pinfunction "DIO8/SLEEP_RQ/DTR_10") (pintype "passive"))
    )
    (net (code "12") (name "/D_N") (class "Default")
      (node (ref "MCU") (pin "45") (pinfunction "PA24_45") (pintype "passive"))
      (node (ref "uUSB") (pin "2") (pinfunction "D-_2") (pintype "passive"))
    )
    (net (code "13") (name "/D_P") (class "Default")
      (node (ref "MCU") (pin "46") (pinfunction "PA25_46") (pintype "passive"))
      (node (ref "uUSB") (pin "3") (pinfunction "D+_3") (pintype "passive"))
    )
    (net (code "14") (name "/Disp_MOSI") (class "Default")
      (node (ref "DISP_CONN1") (pin "2") (pinfunction "SI_2") (pintype "passive"))
      (node (ref "MCU") (pin "29") (pinfunction "PA12_29") (pintype "passive"))
    )
    (net (code "15") (name "/Disp_SCK") (class "Default")
      (node (ref "DISP_CONN1") (pin "1") (pinfunction "SCLK_1") (pintype "passive"))
      (node (ref "MCU") (pin "30") (pinfunction "PA13_30") (pintype "passive"))
    )
    (net (code "16") (name "/Disp_SS") (class "Default")
      (node (ref "DISP_CONN1") (pin "3") (pinfunction "SCS_3") (pintype "passive"))
      (node (ref "MCU") (pin "27") (pinfunction "PB14_27") (pintype "passive"))
    )
    (net (code "17") (name "/GLED_EN") (class "Default")
      (node (ref "MCU") (pin "51") (pinfunction "PA27_51") (pintype "passive"))
      (node (ref "R12") (pin "2") (pinfunction "2_2") (pintype "passive"))
    )
    (net (code "18") (name "/MISO") (class "Default")
      (node (ref "MCU") (pin "23") (pinfunction "PB10_23") (pintype "passive"))
      (node (ref "micro_SD") (pin "7") (pinfunction "DAT0_7") (pintype "passive"))
    )
    (net (code "19") (name "/MOSI") (class "Default")
      (node (ref "MCU") (pin "25") (pinfunction "PB12_25") (pintype "passive"))
      (node (ref "micro_SD") (pin "3") (pinfunction "CMD_3") (pintype "passive"))
    )
    (net (code "20") (name "/RADIO_EN") (class "Default")
      (node (ref "MCU") (pin "59") (pinfunction "PB30_59") (pintype "passive"))
      (node (ref "R23") (pin "2") (pinfunction "2_2") (pintype "passive"))
      (node (ref "TPS62742") (pin "4") (pinfunction "CTRL_4") (pintype "passive"))
    )
    (net (code "21") (name "/RADIO_~{RESET}") (class "Default")
      (node (ref "MCU") (pin "6") (pinfunction "PB05_6") (pintype "passive"))
      (node (ref "R37") (pin "2") (pinfunction "2_2") (pintype "passive"))
      (node (ref "XB24_BS") (pin "6") (pinfunction "~{RESET}_6") (pintype "passive"))
    )
    (net (code "22") (name "/RLED_EN") (class "Default")
      (node (ref "MCU") (pin "53") (pinfunction "PA28_53") (pintype "passive"))
      (node (ref "R10") (pin "2") (pinfunction "2_2") (pintype "passive"))
    )
    (net (code "23") (name "/RTS") (class "Default")
      (node (ref "MCU") (pin "39") (pinfunction "PB16_39") (pintype "passive"))
      (node (ref "XB24_BS") (pin "29") (pinfunction "DIO/~{RTS}_29") (pintype "passive"))
    )
    (net (code "24") (name "/RXD") (class "Default")
      (node (ref "MCU") (pin "20") (pinfunction "PA11_20") (pintype "passive"))
      (node (ref "XB24_BS") (pin "3") (pinfunction "DOUT_3") (pintype "passive"))
    )
    (net (code "25") (name "/RX_STRENGTH") (class "Default")
      (node (ref "MCU") (pin "5") (pinfunction "PB04_5") (pintype "passive"))
      (node (ref "XB24_BS") (pin "7") (pinfunction "DIO10/PWM0/RSSI_7") (pintype "passive"))
    )
    (net (code "26") (name "/SCK") (class "Default")
      (node (ref "MCU") (pin "24") (pinfunction "PB11_24") (pintype "passive"))
      (node (ref "micro_SD") (pin "5") (pinfunction "CLK_5") (pintype "passive"))
    )
    (net (code "27") (name "/SCL") (class "Default")
      (node (ref "DS3231") (pin "16") (pinfunction "SCL_16") (pintype "passive"))
      (node (ref "FRAM1") (pin "6") (pinfunction "SCL_6") (pintype "passive"))
      (node (ref "MCU") (pin "44") (pinfunction "PA23_44") (pintype "passive"))
      (node (ref "R34") (pin "2") (pinfunction "2_2") (pintype "passive"))
    )
    (net (code "28") (name "/SDA") (class "Default")
      (node (ref "DS3231") (pin "15") (pinfunction "SDA_15") (pintype "passive"))
      (node (ref "FRAM1") (pin "5") (pinfunction "SDA_5") (pintype "passive"))
      (node (ref "MCU") (pin "43") (pinfunction "PA22_43") (pintype "passive"))
      (node (ref "R35") (pin "2") (pinfunction "2_2") (pintype "passive"))
    )
    (net (code "29") (name "/SD_CD") (class "Default")
      (node (ref "MCU") (pin "18") (pinfunction "PA09_18") (pintype "passive"))
      (node (ref "R1") (pin "2") (pinfunction "2_2") (pintype "passive"))
      (node (ref "micro_SD") (pin "10") (pinfunction "Switch_Nail_10") (pintype "passive"))
    )
    (net (code "30") (name "/SD_EN") (class "Default")
      (node (ref "MCU") (pin "17") (pinfunction "PA08_17") (pintype "passive"))
      (node (ref "R40") (pin "2") (pinfunction "2_2") (pintype "passive"))
      (node (ref "TPS22919_SD") (pin "3") (pinfunction "ON_3") (pintype "passive"))
    )
    (net (code "31") (name "/SD_SS") (class "Default")
      (node (ref "MCU") (pin "26") (pinfunction "PB13_26") (pintype "passive"))
      (node (ref "micro_SD") (pin "2") (pinfunction "CD/DAT3_2") (pintype "passive"))
    )
    (net (code "32") (name "/SLEEP_STATUS") (class "Default")
      (node (ref "MCU") (pin "42") (pinfunction "PA21_42") (pintype "passive"))
      (node (ref "XB24_BS") (pin "26") (pinfunction "ON/~{SLEEP}_26") (pintype "passive"))
    )
    (net (code "33") (name "/SWDCLK") (class "Default")
      (node (ref "MCU") (pin "57") (pinfunction "PA30_57") (pintype "passive"))
      (node (ref "R33") (pin "1") (pinfunction "1_1") (pintype "passive"))
      (node (ref "SWDIO") (pin "4") (pinfunction "4_4") (pintype "passive"))
    )
    (net (code "34") (name "/SWDIO") (class "Default")
      (node (ref "MCU") (pin "58") (pinfunction "PA31_58") (pintype "passive"))
      (node (ref "SWDIO") (pin "2") (pinfunction "2_2") (pintype "passive"))
    )
    (net (code "35") (name "/TXD") (class "Default")
      (node (ref "MCU") (pin "19") (pinfunction "PA10_19") (pintype "passive"))
      (node (ref "XB24_BS") (pin "4") (pinfunction "DIN/~{CONFIG}_4") (pintype "passive"))
    )
    (net (code "36") (name "/USB_HOST_EN") (class "Default")
      (node (ref "MCU") (pin "50") (pinfunction "PB23_50") (pintype "passive"))
      (node (ref "R32") (pin "1") (pinfunction "1_1") (pintype "passive"))
    )
    (net (code "37") (name "/VBAT_level") (class "Default")
      (node (ref "MCU") (pin "11") (pinfunction "PB08_11") (pintype "passive"))
      (node (ref "R19") (pin "1") (pinfunction "1_1") (pintype "passive"))
      (node (ref "R26") (pin "2") (pinfunction "2_2") (pintype "passive"))
    )
    (net (code "38") (name "/VBat") (class "Default")
      (node (ref "C8") (pin "2") (pinfunction "2_2") (pintype "passive"))
      (node (ref "D3") (pin "1") (pinfunction "A_1") (pintype "passive"))
      (node (ref "MCP73831") (pin "3") (pinfunction "VBAT_3") (pintype "passive"))
      (node (ref "R19") (pin "2") (pinfunction "2_2") (pintype "passive"))
      (node (ref "SW_PWR") (pin "2") (pinfunction "2_2") (pintype "passive"))
    )
    (net (code "39") (name "/VBat_RAW") (class "Default")
      (node (ref "JST_BAT1") (pin "2") (pinfunction "VDD_2") (pintype "passive"))
      (node (ref "SW_PWR") (pin "1") (pinfunction "1_1") (pintype "passive"))
    )
    (net (code "40") (name "/VBus") (class "Default")
      (node (ref "C19") (pin "1") (pinfunction "1_1") (pintype "passive"))
      (node (ref "D2") (pin "1") (pinfunction "A_1") (pintype "passive"))
      (node (ref "R20") (pin "2") (pinfunction "2_2") (pintype "passive"))
      (node (ref "uUSB") (pin "1") (pinfunction "VBUS_1") (pintype "passive"))
    )
    (net (code "41") (name "/VCC") (class "Default")
      (node (ref "C15") (pin "2") (pinfunction "2_2") (pintype "passive"))
      (node (ref "C9") (pin "2") (pinfunction "2_2") (pintype "passive"))
      (node (ref "D1") (pin "1") (pinfunction "A_1") (pintype "passive"))
      (node (ref "D2") (pin "2") (pinfunction "K_2") (pintype "passive"))
      (node (ref "D3") (pin "2") (pinfunction "K_2") (pintype "passive"))
      (node (ref "MCP73831") (pin "4") (pinfunction "VDD_4") (pintype "passive"))
      (node (ref "REG710") (pin "5") (pinfunction "Vin_5") (pintype "passive"))
      (node (ref "TPS62742") (pin "1") (pinfunction "VIN_1") (pintype "passive"))
      (node (ref "TPS62742") (pin "10") (pinfunction "VSEL2_10") (pintype "passive"))
      (node (ref "TPS62742") (pin "11") (pinfunction "VSEL1_11") (pintype "passive"))
      (node (ref "TPS62742") (pin "12") (pinfunction "EN_12") (pintype "passive"))
      (node (ref "TPS62742") (pin "8") (pinfunction "VSEL4_8") (pintype "passive"))
      (node (ref "TPS62742") (pin "9") (pinfunction "VSEL3_9") (pintype "passive"))
    )
    (net (code "42") (name "/VDD_RTC_BACKUP") (class "Default")
      (node (ref "BATT_HOLDER_BS") (pin "1") (pinfunction "+_1") (pintype "passive"))
      (node (ref "C16") (pin "2") (pinfunction "2_2") (pintype "passive"))
      (node (ref "DS3231") (pin "14") (pinfunction "VBAT_14") (pintype "passive"))
    )
    (net (code "43") (name "/VDD_SD") (class "Default")
      (node (ref "C2") (pin "1") (pinfunction "1_1") (pintype "passive"))
      (node (ref "C3") (pin "1") (pinfunction "1_1") (pintype "passive"))
      (node (ref "R1") (pin "1") (pinfunction "1_1") (pintype "passive"))
      (node (ref "R2") (pin "1") (pinfunction "1_1") (pintype "passive"))
      (node (ref "R38") (pin "2") (pinfunction "2_2") (pintype "passive"))
      (node (ref "R4") (pin "1") (pinfunction "1_1") (pintype "passive"))
      (node (ref "TPS22919_SD") (pin "6") (pinfunction "VOUT_6") (pintype "passive"))
      (node (ref "micro_SD") (pin "4") (pinfunction "VDD_4") (pintype "passive"))
    )
    (net (code "44") (name "/V_Disp") (class "Default")
      (node (ref "C4") (pin "2") (pinfunction "2_2") (pintype "passive"))
      (node (ref "C5") (pin "2") (pinfunction "2_2") (pintype "passive"))
      (node (ref "C6") (pin "2") (pinfunction "2_2") (pintype "passive"))
      (node (ref "C7") (pin "2") (pinfunction "2_2") (pintype "passive"))
      (node (ref "DISP_CONN1") (pin "5") (pinfunction "DSIP_5") (pintype "passive"))
      (node (ref "DISP_CONN1") (pin "6") (pinfunction "VDDA_6") (pintype "passive"))
      (node (ref "DISP_CONN1") (pin "7") (pinfunction "VDD_7") (pintype "passive"))
      (node (ref "DISP_MODE1") (pin "3") (pinfunction "DISP_VDD_3") (pintype "passive"))
      (node (ref "REG710") (pin "1") (pinfunction "Vout_1") (pintype "passive"))
    )
    (net (code "45") (name "/Vbus_detect") (class "Default")
      (node (ref "MCU") (pin "12") (pinfunction "PB09_12") (pintype "passive"))
      (node (ref "R20") (pin "1") (pinfunction "1_1") (pintype "passive"))
      (node (ref "R27") (pin "2") (pinfunction "2_2") (pintype "passive"))
    )
    (net (code "46") (name "/WAKE_ALARM") (class "Default")
      (node (ref "DS3231") (pin "3") (pinfunction "INT/SQW_3") (pintype "passive"))
      (node (ref "MCU") (pin "35") (pinfunction "PA16_35") (pintype "passive"))
      (node (ref "R21") (pin "1") (pinfunction "1_1") (pintype "passive"))
    )
    (net (code "47") (name "/gLED2_EN") (class "Default")
      (node (ref "MCU") (pin "60") (pinfunction "PB31_60") (pintype "passive"))
      (node (ref "R29") (pin "2") (pinfunction "2_2") (pintype "passive"))
    )
    (net (code "48") (name "/rLED2_EN") (class "Default")
      (node (ref "MCU") (pin "61") (pinfunction "PB00_61") (pintype "passive"))
      (node (ref "R22") (pin "2") (pinfunction "2_2") (pintype "passive"))
    )
    (net (code "49") (name "/~{RESET}") (class "Default")
      (node (ref "C34") (pin "2") (pinfunction "2_2") (pintype "passive"))
      (node (ref "MCU") (pin "52") (pinfunction "RESETN_52") (pintype "passive"))
      (node (ref "PWR_GOOD_MCU_RESET") (pin "2") (pinfunction "2_2") (pintype "passive"))
      (node (ref "R39") (pin "1") (pinfunction "1_1") (pintype "passive"))
      (node (ref "SWDIO") (pin "10") (pinfunction "10_10") (pintype "passive"))
    )
    (net (code "50") (name "GND") (class "Default")
      (node (ref "BATT_HOLDER_BS") (pin "2") (pinfunction "-_2") (pintype "passive"))
      (node (ref "Back") (pin "2") (pinfunction "2_2") (pintype "passive"))
      (node (ref "C10") (pin "2") (pinfunction "2_2") (pintype "passive"))
      (node (ref "C11") (pin "1") (pinfunction "1_1") (pintype "passive"))
      (node (ref "C12") (pin "1") (pinfunction "1_1") (pintype "passive"))
      (node (ref "C13") (pin "1") (pinfunction "1_1") (pintype "passive"))
      (node (ref "C14") (pin "1") (pinfunction "1_1") (pintype "passive"))
      (node (ref "C15") (pin "1") (pinfunction "1_1") (pintype "passive"))
      (node (ref "C16") (pin "1") (pinfunction "1_1") (pintype "passive"))
      (node (ref "C17") (pin "1") (pinfunction "1_1") (pintype "passive"))
      (node (ref "C18") (pin "2") (pinfunction "2_2") (pintype "passive"))
      (node (ref "C19") (pin "2") (pinfunction "2_2") (pintype "passive"))
      (node (ref "C2") (pin "2") (pinfunction "2_2") (pintype "passive"))
      (node (ref "C20") (pin "1") (pinfunction "1_1") (pintype "passive"))
      (node (ref "C21") (pin "1") (pinfunction "1_1") (pintype "passive"))
      (node (ref "C22") (pin "1") (pinfunction "1_1") (pintype "passive"))
      (node (ref "C23") (pin "2") (pinfunction "2_2") (pintype "passive"))
      (node (ref "C24") (pin "1") (pinfunction "1_1") (pintype "passive"))
      (node (ref "C25") (pin "2") (pinfunction "2_2") (pintype "passive"))
      (node (ref "C26") (pin "1") (pinfunction "1_1") (pintype "passive"))
      (node (ref "C27") (pin "2") (pinfunction "2_2") (pintype "passive"))
      (node (ref "C28") (pin "2") (pinfunction "2_2") (pintype "passive"))
      (node (ref "C29") (pin "2") (pinfunction "2_2") (pintype "passive"))
      (node (ref "C3") (pin "2") (pinfunction "2_2") (pintype "passive"))
      (node (ref "C30") (pin "2") (pinfunction "2_2") (pintype "passive"))
      (node (ref "C31") (pin "2") (pinfunction "2_2") (pintype "passive"))
      (node (ref "C32") (pin "2") (pinfunction "2_2") (pintype "passive"))
      (node (ref "C33") (pin "2") (pinfunction "2_2") (pintype "passive"))
      (node (ref "C34") (pin "1") (pinfunction "1_1") (pintype "passive"))
      (node (ref "C35") (pin "1") (pinfunction "1_1") (pintype "passive"))
      (node (ref "C36") (pin "1") (pinfunction "1_1") (pintype "passive"))
      (node (ref "C4") (pin "1") (pinfunction "1_1") (pintype "passive"))
      (node (ref "C5") (pin "1") (pinfunction "1_1") (pintype "passive"))
      (node (ref "C6") (pin "1") (pinfunction "1_1") (pintype "passive"))
      (node (ref "C7") (pin "1") (pinfunction "1_1") (pintype "passive"))
      (node (ref "C8") (pin "1") (pinfunction "1_1") (pintype "passive"))
      (node (ref "C9") (pin "1") (pinfunction "1_1") (pintype "passive"))
      (node (ref "DISP_CONN1") (pin "10") (pinfunction "VSSA_10") (pintype "passive"))
      (node (ref "DISP_CONN1") (pin "9") (pinfunction "VSS_9") (pintype "passive"))
      (node (ref "DISP_MODE1") (pin "1") (pinfunction "GND_1") (pintype "passive"))
      (node (ref "DS3231") (pin "10") (pinfunction "N.C._10") (pintype "passive"))
      (node (ref "DS3231") (pin "11") (pinfunction "N.C._11") (pintype "passive"))
      (node (ref "DS3231") (pin "12") (pinfunction "N.C._12") (pintype "passive"))
      (node (ref "DS3231") (pin "13") (pinfunction "GND_13") (pintype "passive"))
      (node (ref "DS3231") (pin "5") (pinfunction "N.C._5") (pintype "passive"))
      (node (ref "DS3231") (pin "6") (pinfunction "N.C._6") (pintype "passive"))
      (node (ref "DS3231") (pin "7") (pinfunction "N.C._7") (pintype "passive"))
      (node (ref "DS3231") (pin "8") (pinfunction "N.C._8") (pintype "passive"))
      (node (ref "DS3231") (pin "9") (pinfunction "N.C._9") (pintype "passive"))
      (node (ref "DUAL_NCH_1") (pin "1") (pinfunction "S1_1") (pintype "passive"))
      (node (ref "DUAL_NCH_1") (pin "3") (pinfunction "S2_3") (pintype "passive"))
      (node (ref "DUAL_NCH_2") (pin "1") (pinfunction "S1_1") (pintype "passive"))
      (node (ref "DUAL_NCH_2") (pin "3") (pinfunction "S2_3") (pintype "passive"))
      (node (ref "Down") (pin "2") (pinfunction "2_2") (pintype "passive"))
      (node (ref "FRAM1") (pin "4") (pinfunction "VSS_4") (pintype "passive"))
      (node (ref "JST_BAT1") (pin "1") (pinfunction "GND_1") (pintype "passive"))
      (node (ref "MCP73831") (pin "2") (pinfunction "VSS_2") (pintype "passive"))
      (node (ref "MCU") (pin "22") (pinfunction "GND_22") (pintype "passive"))
      (node (ref "MCU") (pin "33") (pinfunction "GND_33") (pintype "passive"))
      (node (ref "MCU") (pin "47") (pinfunction "GND_47") (pintype "passive"))
      (node (ref "MCU") (pin "54") (pinfunction "GND_54") (pintype "passive"))
      (node (ref "MCU") (pin "7") (pinfunction "GNDANA_7") (pintype "passive"))
      (node (ref "Menu/OK") (pin "2") (pinfunction "2_2") (pintype "passive"))
      (node (ref "R11") (pin "1") (pinfunction "1_1") (pintype "passive"))
      (node (ref "R14") (pin "1") (pinfunction "1_1") (pintype "passive"))
      (node (ref "R23") (pin "1") (pinfunction "1_1") (pintype "passive"))
      (node (ref "R24") (pin "1") (pinfunction "1_1") (pintype "passive"))
      (node (ref "R25") (pin "2") (pinfunction "2_2") (pintype "passive"))
      (node (ref "R26") (pin "1") (pinfunction "1_1") (pintype "passive"))
      (node (ref "R27") (pin "1") (pinfunction "1_1") (pintype "passive"))
      (node (ref "R3") (pin "2") (pinfunction "2_2") (pintype "passive"))
      (node (ref "R30") (pin "2") (pinfunction "2_2") (pintype "passive"))
      (node (ref "R40") (pin "1") (pinfunction "1_1") (pintype "passive"))
      (node (ref "REG710") (pin "2") (pinfunction "GND_2") (pintype "passive"))
      (node (ref "RESET") (pin "2") (pinfunction "2_2") (pintype "passive"))
      (node (ref "RTC_RESET") (pin "1") (pinfunction "1_1") (pintype "passive"))
      (node (ref "SWDIO") (pin "3") (pinfunction "3_3") (pintype "passive"))
      (node (ref "SWDIO") (pin "5") (pinfunction "5_5") (pintype "passive"))
      (node (ref "SWDIO") (pin "9") (pinfunction "9_9") (pintype "passive"))
      (node (ref "TPS22919_SD") (pin "2") (pinfunction "GND_2") (pintype "passive"))
      (node (ref "TPS62742") (pin "3") (pinfunction "GND_3") (pintype "passive"))
      (node (ref "Up") (pin "2") (pinfunction "2_2") (pintype "passive"))
      (node (ref "XB24_BS") (pin "1") (pinfunction "GND_1") (pintype "passive"))
      (node (ref "XB24_BS") (pin "11") (pinfunction "GND_11") (pintype "passive"))
      (node (ref "XB24_BS") (pin "13") (pinfunction "GND_13") (pintype "passive"))
      (node (ref "XB24_BS") (pin "22") (pinfunction "GND_22") (pintype "passive"))
      (node (ref "XB24_BS") (pin "35") (pinfunction "GND_35") (pintype "passive"))
      (node (ref "micro_SD") (pin "6") (pinfunction "VSS_6") (pintype "passive"))
      (node (ref "micro_SD") (pin "9") (pinfunction "DETECT_Nail_9") (pintype "passive"))
      (node (ref "uUSB") (pin "5") (pinfunction "GND_5") (pintype "passive"))
    )
    (net (code "51") (name "Net-(D1-K)") (class "Default")
      (node (ref "D1") (pin "2") (pinfunction "K_2") (pintype "passive"))
      (node (ref "R18") (pin "1") (pinfunction "1_1") (pintype "passive"))
    )
    (net (code "52") (name "Net-(DISP_CONN1-EXTMODE)") (class "Default")
      (node (ref "DISP_CONN1") (pin "8") (pinfunction "EXTMODE_8") (pintype "passive"))
      (node (ref "DISP_MODE1") (pin "2") (pinfunction "EXTMODE_2") (pintype "passive"))
    )
    (net (code "53") (name "Net-(DS3231-RST)") (class "Default")
      (node (ref "DS3231") (pin "4") (pinfunction "RST_4") (pintype "passive"))
      (node (ref "RTC_RESET") (pin "2") (pinfunction "2_2") (pintype "passive"))
    )
    (net (code "54") (name "Net-(DUAL_NCH_1-G1)") (class "Default")
      (node (ref "DUAL_NCH_1") (pin "2") (pinfunction "G1_2") (pintype "passive"))
      (node (ref "R10") (pin "1") (pinfunction "1_1") (pintype "passive"))
      (node (ref "R11") (pin "2") (pinfunction "2_2") (pintype "passive"))
    )
    (net (code "55") (name "Net-(DUAL_NCH_1-G2)") (class "Default")
      (node (ref "DUAL_NCH_1") (pin "4") (pinfunction "G2_4") (pintype "passive"))
      (node (ref "R12") (pin "1") (pinfunction "1_1") (pintype "passive"))
      (node (ref "R14") (pin "2") (pinfunction "2_2") (pintype "passive"))
    )
    (net (code "56") (name "Net-(DUAL_NCH_2-G1)") (class "Default")
      (node (ref "DUAL_NCH_2") (pin "2") (pinfunction "G1_2") (pintype "passive"))
      (node (ref "R22") (pin "1") (pinfunction "1_1") (pintype "passive"))
      (node (ref "R25") (pin "1") (pinfunction "1_1") (pintype "passive"))
    )
    (net (code "57") (name "Net-(DUAL_NCH_2-G2)") (class "Default")
      (node (ref "DUAL_NCH_2") (pin "4") (pinfunction "G2_4") (pintype "passive"))
      (node (ref "R29") (pin "1") (pinfunction "1_1") (pintype "passive"))
      (node (ref "R30") (pin "1") (pinfunction "1_1") (pintype "passive"))
    )
    (net (code "58") (name "Net-(FRAM1-A0)") (class "Default")
      (node (ref "FRAM1") (pin "1") (pinfunction "A0_1") (pintype "passive"))
      (node (ref "R8") (pin "1") (pinfunction "1_1") (pintype "passive"))
    )
    (net (code "59") (name "Net-(MCP73831-PROG)") (class "Default")
      (node (ref "MCP73831") (pin "5") (pinfunction "PROG_5") (pintype "passive"))
      (node (ref "R24") (pin "2") (pinfunction "2_2") (pintype "passive"))
    )
    (net (code "60") (name "Net-(MCP73831-STAT)") (class "Default")
      (node (ref "MCP73831") (pin "1") (pinfunction "STAT_1") (pintype "passive"))
      (node (ref "R18") (pin "2") (pinfunction "2_2") (pintype "passive"))
    )
    (net (code "61") (name "Net-(MCU-PA00)") (class "Default")
      (node (ref "C23") (pin "1") (pinfunction "1_1") (pintype "passive"))
      (node (ref "MCU") (pin "1") (pinfunction "PA00_1") (pintype "passive"))
      (node (ref "Y1") (pin "2") (pinfunction "OSC2_2") (pintype "passive"))
    )
    (net (code "62") (name "Net-(MCU-PA01)") (class "Default")
      (node (ref "C25") (pin "1") (pinfunction "1_1") (pintype "passive"))
      (node (ref "MCU") (pin "2") (pinfunction "PA01_2") (pintype "passive"))
      (node (ref "Y1") (pin "1") (pinfunction "OSC1_1") (pintype "passive"))
    )
    (net (code "63") (name "Net-(MCU-VDDANA)") (class "Default")
      (node (ref "C29") (pin "1") (pinfunction "1_1") (pintype "passive"))
      (node (ref "C30") (pin "1") (pinfunction "1_1") (pintype "passive"))
      (node (ref "FB_1") (pin "2") (pinfunction "2_2") (pintype "passive"))
      (node (ref "MCU") (pin "8") (pinfunction "VDDANA_8") (pintype "passive"))
    )
    (net (code "64") (name "Net-(R36-Pad1)") (class "Default")
      (node (ref "R36") (pin "1") (pinfunction "1_1") (pintype "passive"))
      (node (ref "R39") (pin "2") (pinfunction "2_2") (pintype "passive"))
      (node (ref "RESET") (pin "1") (pinfunction "1_1") (pintype "passive"))
    )
    (net (code "65") (name "Net-(REG710-Cp+)") (class "Default")
      (node (ref "C1") (pin "2") (pinfunction "2_2") (pintype "passive"))
      (node (ref "REG710") (pin "6") (pinfunction "Cp+_6") (pintype "passive"))
    )
    (net (code "66") (name "Net-(REG710-Cp-)") (class "Default")
      (node (ref "C1") (pin "1") (pinfunction "1_1") (pintype "passive"))
      (node (ref "REG710") (pin "4") (pinfunction "Cp-_4") (pintype "passive"))
    )
    (net (code "67") (name "Net-(TPS22919_SD-CT)") (class "Default")
      (node (ref "C33") (pin "1") (pinfunction "1_1") (pintype "passive"))
      (node (ref "TPS22919_SD") (pin "4") (pinfunction "CT_4") (pintype "passive"))
    )
    (net (code "68") (name "Net-(TPS22919_SD-QOD)") (class "Default")
      (node (ref "R38") (pin "1") (pinfunction "1_1") (pintype "passive"))
      (node (ref "TPS22919_SD") (pin "5") (pinfunction "QOD_5") (pintype "passive"))
    )
    (net (code "69") (name "Net-(TPS62742-PG)") (class "Default")
      (node (ref "PWR_GOOD_MCU_RESET") (pin "1") (pinfunction "1_1") (pintype "passive"))
      (node (ref "R28") (pin "1") (pinfunction "1_1") (pintype "passive"))
      (node (ref "TPS62742") (pin "7") (pinfunction "PG_7") (pintype "passive"))
    )
    (net (code "70") (name "Net-(TPS62742-SW)") (class "Default")
      (node (ref "L2") (pin "1") (pinfunction "1_1") (pintype "passive"))
      (node (ref "TPS62742") (pin "2") (pinfunction "SW_2") (pintype "passive"))
    )
    (net (code "71") (name "Net-(micro_SD-DAT1)") (class "Default")
      (node (ref "R2") (pin "2") (pinfunction "2_2") (pintype "passive"))
      (node (ref "micro_SD") (pin "8") (pinfunction "DAT1_8") (pintype "passive"))
    )
    (net (code "72") (name "Net-(micro_SD-DAT2)") (class "Default")
      (node (ref "R4") (pin "2") (pinfunction "2_2") (pintype "passive"))
      (node (ref "micro_SD") (pin "1") (pinfunction "DAT2_1") (pintype "passive"))
    )
    (net (code "73") (name "Net-(rgLED_BS_1-G_AN+)") (class "Default")
      (node (ref "R5") (pin "1") (pinfunction "1_1") (pintype "passive"))
      (node (ref "rgLED_BS_1") (pin "1") (pinfunction "G_AN+_1") (pintype "passive"))
    )
    (net (code "74") (name "Net-(rgLED_BS_1-G_CAT)") (class "Default")
      (node (ref "DUAL_NCH_1") (pin "5") (pinfunction "D2_5") (pintype "passive"))
      (node (ref "DUAL_NCH_1") (pin "6") (pinfunction "D2_6") (pintype "passive"))
      (node (ref "rgLED_BS_1") (pin "2") (pinfunction "G_CAT_2") (pintype "passive"))
    )
    (net (code "75") (name "Net-(rgLED_BS_1-R_AN)") (class "Default")
      (node (ref "R7") (pin "1") (pinfunction "1_1") (pintype "passive"))
      (node (ref "rgLED_BS_1") (pin "3") (pinfunction "R_AN_3") (pintype "passive"))
    )
    (net (code "76") (name "Net-(rgLED_BS_1-R_CAT)") (class "Default")
      (node (ref "DUAL_NCH_1") (pin "7") (pinfunction "D1_7") (pintype "passive"))
      (node (ref "DUAL_NCH_1") (pin "8") (pinfunction "D1_8") (pintype "passive"))
      (node (ref "rgLED_BS_1") (pin "4") (pinfunction "R_CAT_4") (pintype "passive"))
    )
    (net (code "77") (name "Net-(rgLED_BS_2-G_AN+)") (class "Default")
      (node (ref "R16") (pin "1") (pinfunction "1_1") (pintype "passive"))
      (node (ref "rgLED_BS_2") (pin "1") (pinfunction "G_AN+_1") (pintype "passive"))
    )
    (net (code "78") (name "Net-(rgLED_BS_2-G_CAT)") (class "Default")
      (node (ref "DUAL_NCH_2") (pin "5") (pinfunction "D2_5") (pintype "passive"))
      (node (ref "DUAL_NCH_2") (pin "6") (pinfunction "D2_6") (pintype "passive"))
      (node (ref "rgLED_BS_2") (pin "2") (pinfunction "G_CAT_2") (pintype "passive"))
    )
    (net (code "79") (name "Net-(rgLED_BS_2-R_AN)") (class "Default")
      (node (ref "R17") (pin "1") (pinfunction "1_1") (pintype "passive"))
      (node (ref "rgLED_BS_2") (pin "3") (pinfunction "R_AN_3") (pintype "passive"))
    )
    (net (code "80") (name "Net-(rgLED_BS_2-R_CAT)") (class "Default")
      (node (ref "DUAL_NCH_2") (pin "7") (pinfunction "D1_7") (pintype "passive"))
      (node (ref "DUAL_NCH_2") (pin "8") (pinfunction "D1_8") (pintype "passive"))
      (node (ref "rgLED_BS_2") (pin "4") (pinfunction "R_CAT_4") (pintype "passive"))
    )
    (net (code "81") (name "Net-(uUSB-ID)") (class "Default")
      (node (ref "R31") (pin "1") (pinfunction "1_1") (pintype "passive"))
      (node (ref "R32") (pin "2") (pinfunction "2_2") (pintype "passive"))
      (node (ref "uUSB") (pin "4") (pinfunction "ID_4") (pintype "passive"))
    )
    (net (code "82") (name "unconnected-(DS3231-32kHz-Pad1)") (class "Default")
      (node (ref "DS3231") (pin "1") (pinfunction "32kHz_1") (pintype "passive"))
    )
    (net (code "83") (name "unconnected-(FRAM1-A1-Pad2)") (class "Default")
      (node (ref "FRAM1") (pin "2") (pinfunction "A1_2") (pintype "passive"))
    )
    (net (code "84") (name "unconnected-(FRAM1-A2-Pad3)") (class "Default")
      (node (ref "FRAM1") (pin "3") (pinfunction "A2_3") (pintype "passive"))
    )
    (net (code "85") (name "unconnected-(FRAM1-WP-Pad7)") (class "Default")
      (node (ref "FRAM1") (pin "7") (pinfunction "WP_7") (pintype "passive"))
    )
    (net (code "86") (name "unconnected-(MCU-PA04-Pad13)") (class "Default")
      (node (ref "MCU") (pin "13") (pinfunction "PA04_13") (pintype "passive"))
    )
    (net (code "87") (name "unconnected-(MCU-PA05-Pad14)") (class "Default")
      (node (ref "MCU") (pin "14") (pinfunction "PA05_14") (pintype "passive"))
    )
    (net (code "88") (name "unconnected-(MCU-PA06-Pad15)") (class "Default")
      (node (ref "MCU") (pin "15") (pinfunction "PA06_15") (pintype "passive"))
    )
    (net (code "89") (name "unconnected-(MCU-PA07-Pad16)") (class "Default")
      (node (ref "MCU") (pin "16") (pinfunction "PA07_16") (pintype "passive"))
    )
    (net (code "90") (name "unconnected-(MCU-PA14-Pad31)") (class "Default")
      (node (ref "MCU") (pin "31") (pinfunction "PA14_31") (pintype "passive"))
    )
    (net (code "91") (name "unconnected-(MCU-PB01-Pad62)") (class "Default")
      (node (ref "MCU") (pin "62") (pinfunction "PB01_62") (pintype "passive"))
    )
    (net (code "92") (name "unconnected-(MCU-PB02-Pad63)") (class "Default")
      (node (ref "MCU") (pin "63") (pinfunction "PB02_63") (pintype "passive"))
    )
    (net (code "93") (name "unconnected-(MCU-PB03-Pad64)") (class "Default")
      (node (ref "MCU") (pin "64") (pinfunction "PB03_64") (pintype "passive"))
    )
    (net (code "94") (name "unconnected-(MCU-PB06-Pad9)") (class "Default")
      (node (ref "MCU") (pin "9") (pinfunction "PB06_9") (pintype "passive"))
    )
    (net (code "95") (name "unconnected-(MCU-PB07-Pad10)") (class "Default")
      (node (ref "MCU") (pin "10") (pinfunction "PB07_10") (pintype "passive"))
    )
    (net (code "96") (name "unconnected-(MCU-PB22-Pad49)") (class "Default")
      (node (ref "MCU") (pin "49") (pinfunction "PB22_49") (pintype "passive"))
    )
    (net (code "97") (name "unconnected-(SWDIO-Pad6)") (class "Default")
      (node (ref "SWDIO") (pin "6") (pinfunction "6_6") (pintype "passive"))
    )
    (net (code "98") (name "unconnected-(SWDIO-Pad7)") (class "Default")
      (node (ref "SWDIO") (pin "7") (pinfunction "7_7") (pintype "passive"))
    )
    (net (code "99") (name "unconnected-(SWDIO-Pad8)") (class "Default")
      (node (ref "SWDIO") (pin "8") (pinfunction "8_8") (pintype "passive"))
    )
    (net (code "100") (name "unconnected-(SW_PWR-Pad3)") (class "Default")
      (node (ref "SW_PWR") (pin "3") (pinfunction "3_3") (pintype "passive"))
    )
    (net (code "101") (name "unconnected-(XB24_BS-DIO0{slash}AD0-Pad33)") (class "Default")
      (node (ref "XB24_BS") (pin "33") (pinfunction "DIO0/AD0_33") (pintype "passive"))
    )
    (net (code "102") (name "unconnected-(XB24_BS-DIO1{slash}AD1-Pad32)") (class "Default")
      (node (ref "XB24_BS") (pin "32") (pinfunction "DIO1/AD1_32") (pintype "passive"))
    )
    (net (code "103") (name "unconnected-(XB24_BS-DIO2{slash}AD2-Pad31)") (class "Default")
      (node (ref "XB24_BS") (pin "31") (pinfunction "DIO2/AD2_31") (pintype "passive"))
    )
    (net (code "104") (name "unconnected-(XB24_BS-DIO3{slash}AD3-Pad30)") (class "Default")
      (node (ref "XB24_BS") (pin "30") (pinfunction "DIO3/AD3_30") (pintype "passive"))
    )
    (net (code "105") (name "unconnected-(XB24_BS-DIO4-Pad24)") (class "Default")
      (node (ref "XB24_BS") (pin "24") (pinfunction "DIO4_24") (pintype "passive"))
    )
    (net (code "106") (name "unconnected-(XB24_BS-DIO5{slash}ASSOC-Pad28)") (class "Default")
      (node (ref "XB24_BS") (pin "28") (pinfunction "DIO5/ASSOC_28") (pintype "passive"))
    )
    (net (code "107") (name "unconnected-(XB24_BS-DIO12-Pad5)") (class "Default")
      (node (ref "XB24_BS") (pin "5") (pinfunction "DIO12_5") (pintype "passive"))
    )
    (net (code "108") (name "unconnected-(XB24_BS-DOI11{slash}PWM1-Pad8)") (class "Default")
      (node (ref "XB24_BS") (pin "8") (pinfunction "DOI11/PWM1_8") (pintype "passive"))
    )
    (net (code "109") (name "unconnected-(XB24_BS-N.C.-Pad9)") (class "Default")
      (node (ref "XB24_BS") (pin "9") (pinfunction "N.C._9") (pintype "passive"))
    )
    (net (code "110") (name "unconnected-(XB24_BS-N.C.-Pad18)") (class "Default")
      (node (ref "XB24_BS") (pin "18") (pinfunction "N.C._18") (pintype "passive"))
    )
    (net (code "111") (name "unconnected-(XB24_BS-N.C.-Pad19)") (class "Default")
      (node (ref "XB24_BS") (pin "19") (pinfunction "N.C._19") (pintype "passive"))
    )
    (net (code "112") (name "unconnected-(XB24_BS-N.C.-Pad20)") (class "Default")
      (node (ref "XB24_BS") (pin "20") (pinfunction "N.C._20") (pintype "passive"))
    )
    (net (code "113") (name "unconnected-(XB24_BS-N.C.-Pad21)") (class "Default")
      (node (ref "XB24_BS") (pin "21") (pinfunction "N.C._21") (pintype "passive"))
    )
    (net (code "114") (name "unconnected-(XB24_BS-N.C.-Pad23)") (class "Default")
      (node (ref "XB24_BS") (pin "23") (pinfunction "N.C._23") (pintype "passive"))
    )
    (net (code "115") (name "unconnected-(XB24_BS-N.C.-Pad34)") (class "Default")
      (node (ref "XB24_BS") (pin "34") (pinfunction "N.C._34") (pintype "passive"))
    )
    (net (code "116") (name "unconnected-(XB24_BS-N.C.-Pad37)") (class "Default")
      (node (ref "XB24_BS") (pin "37") (pinfunction "N.C._37") (pintype "passive"))
    )
    (net (code "117") (name "unconnected-(XB24_BS-RF-Pad36)") (class "Default")
      (node (ref "XB24_BS") (pin "36") (pinfunction "RF_36") (pintype "passive"))
    )
    (net (code "118") (name "unconnected-(XB24_BS-SPI_CLK-Pad14)") (class "Default")
      (node (ref "XB24_BS") (pin "14") (pinfunction "SPI_CLK_14") (pintype "passive"))
    )
    (net (code "119") (name "unconnected-(XB24_BS-SPI_MISO-Pad17)") (class "Default")
      (node (ref "XB24_BS") (pin "17") (pinfunction "SPI_MISO_17") (pintype "passive"))
    )
    (net (code "120") (name "unconnected-(XB24_BS-SPI_MOSI-Pad16)") (class "Default")
      (node (ref "XB24_BS") (pin "16") (pinfunction "SPI_MOSI_16") (pintype "passive"))
    )
    (net (code "121") (name "unconnected-(XB24_BS-SPI_~{SSEL}-Pad15)") (class "Default")
      (node (ref "XB24_BS") (pin "15") (pinfunction "SPI_~{SSEL}_15") (pintype "passive"))
    )
    (net (code "122") (name "unconnected-(XB24_BS-VREF-Pad27)") (class "Default")
      (node (ref "XB24_BS") (pin "27") (pinfunction "VREF_27") (pintype "passive"))
    )
    (net (code "123") (name "unconnected-(XB24_BS-~{SPI_ATTN{slash}BOOTMODE}-Pad12)") (class "Default")
      (node (ref "XB24_BS") (pin "12") (pinfunction "~{SPI_ATTN/BOOTMODE}_12") (pintype "passive"))
    )
  )
)
